# Power.net
KiCad netlist of a schematic drawn in Altium Designer
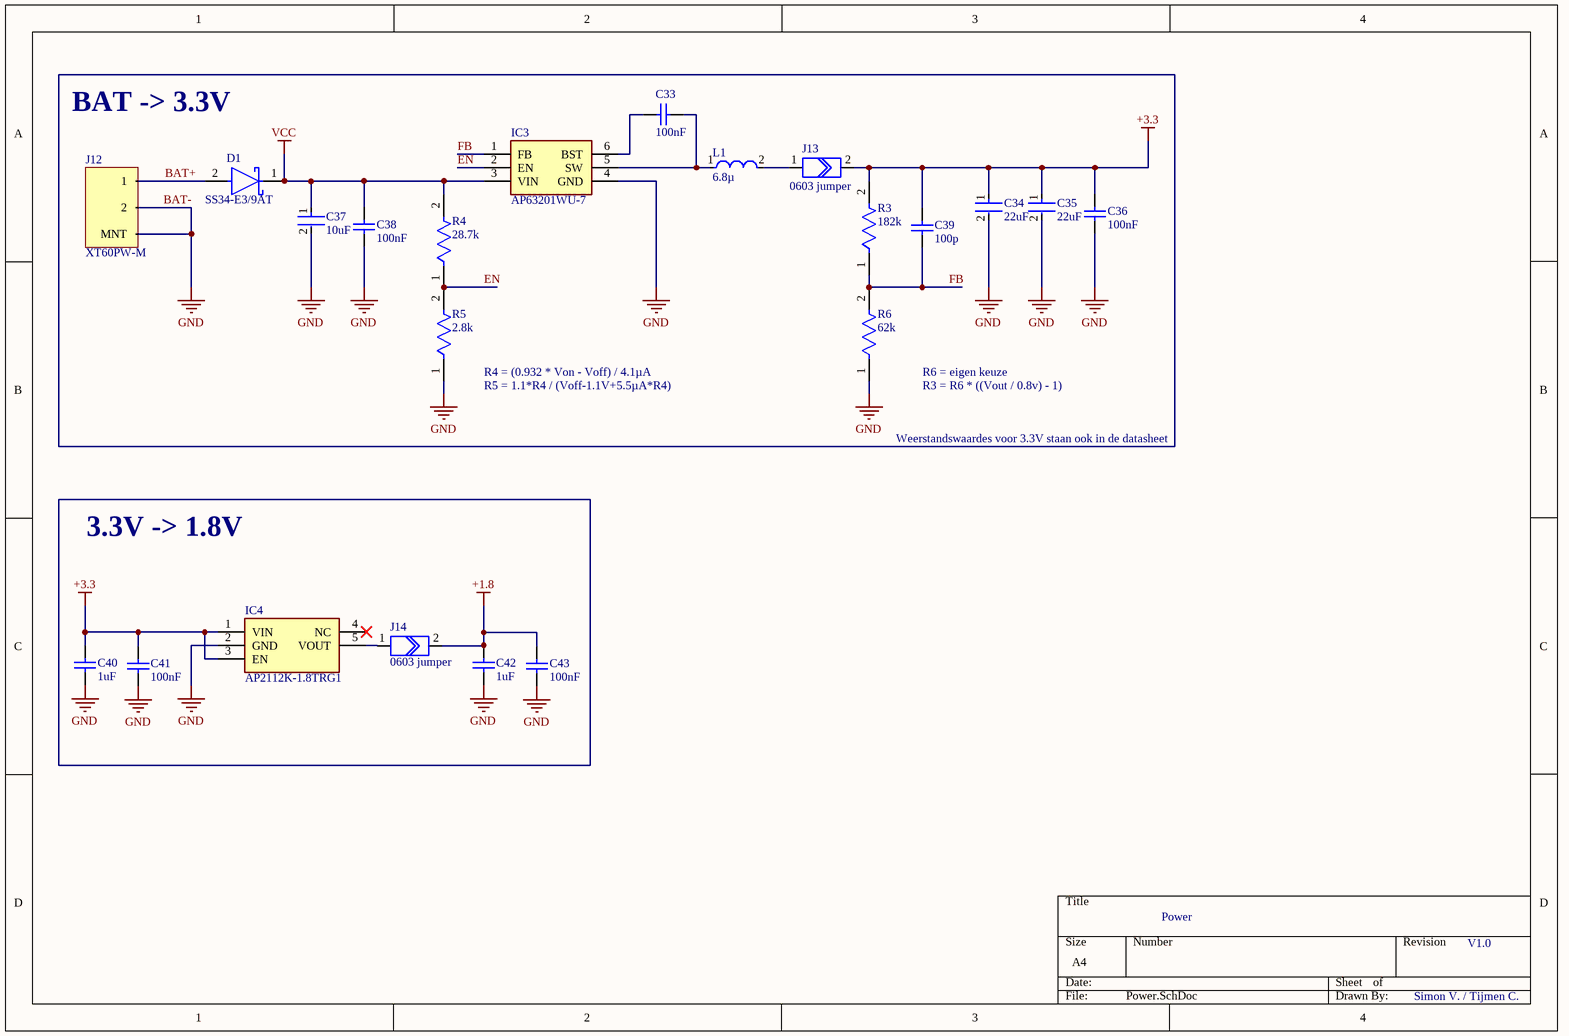
[diagram p0: Power.SchDoc]

(export (version "E")
  (design (tool "Eeschema 10.0.6"))
  (components
    (comp (ref "C33")
      (value "100nF")
      (footprint "CAPC1608X92X38ML15T08")
      (fields (field (name "PART NUMBER") "VJ0603Y104MXXAC") (field (name "MANUFACTURER") "Vitramon"))
      (libsource (lib "Altium Content Vault") (part "CAP"))
    )
    (comp (ref "C34")
      (value "22uF")
      (footprint "FP-GRM188-0_2-IPC_A")
      (description "Multilayer Ceramic Capacitor 22uF 20% 16V X5R 0603 Paper T/R")
      (libsource (lib "Altium Content Vault") (part "02cd4be3c70576c341d710602a673aa"))
    )
    (comp (ref "C35")
      (value "22uF")
      (footprint "FP-GRM188-0_2-IPC_A")
      (description "Multilayer Ceramic Capacitor 22uF 20% 16V X5R 0603 Paper T/R")
      (libsource (lib "Altium Content Vault") (part "02cd4be3c70576c341d710602a673aa"))
    )
    (comp (ref "C36")
      (value "100nF")
      (footprint "CAPC1608X92X38ML15T08")
      (fields (field (name "PART NUMBER") "VJ0603Y104MXXAC") (field (name "MANUFACTURER") "Vitramon"))
      (libsource (lib "Altium Content Vault") (part "CAP"))
    )
    (comp (ref "C37")
      (value "10uF")
      (footprint "FP-ZRB18AR61E106ME01L-MFG")
      (description "CAP CER 10UF 25V X5R 0603")
      (fields (field (name "VOLTAGE") "25V") (field (name "TOLERANCE") "20%"))
      (libsource (lib "Altium Content Vault") (part "b4654b650e69147ec39a6b967a45e02"))
    )
    (comp (ref "C38")
      (value "100nF")
      (footprint "CAPC1608X92X38ML15T08")
      (fields (field (name "PART NUMBER") "VJ0603Y104MXXAC") (field (name "MANUFACTURER") "Vitramon"))
      (libsource (lib "Altium Content Vault") (part "CAP"))
    )
    (comp (ref "C39")
      (value "100p")
      (footprint "CAPC1608X92X38LL15T08")
      (fields (field (name "MANUFACTURER") "Vitramon") (field (name "PART NUMBER") "VJ0603A101FXAAC"))
      (libsource (lib "Altium Content Vault") (part "CAP"))
    )
    (comp (ref "C40")
      (value "1uF")
      (footprint "CAPC1608X90X35NL15T15")
      (fields
        (field (name "PART NUMBER") "0603YD105MAT2A")
        (field (name "MANUFACTURER") "AVX Interconnect / Elco")
      )
      (libsource (lib "Altium Content Vault") (part "CAP"))
    )
    (comp (ref "C41")
      (value "100nF")
      (footprint "CAPC1608X92X38ML15T08")
      (fields (field (name "PART NUMBER") "VJ0603Y104MXXAC") (field (name "MANUFACTURER") "Vitramon"))
      (libsource (lib "Altium Content Vault") (part "CAP"))
    )
    (comp (ref "C42")
      (value "1uF")
      (footprint "CAPC1608X90X35NL15T15")
      (fields
        (field (name "PART NUMBER") "0603YD105MAT2A")
        (field (name "MANUFACTURER") "AVX Interconnect / Elco")
      )
      (libsource (lib "Altium Content Vault") (part "CAP"))
    )
    (comp (ref "C43")
      (value "100nF")
      (footprint "CAPC1608X92X38ML15T08")
      (fields (field (name "PART NUMBER") "VJ0603Y104MXXAC") (field (name "MANUFACTURER") "Vitramon"))
      (libsource (lib "Altium Content Vault") (part "CAP"))
    )
    (comp (ref "D1")
      (value "SS34-E3/9AT")
      (footprint "FP-SMC-MFG")
      (description "DIODE SCHOTTKY 40V 3A DO214AB")
      (libsource (lib "Altium Content Vault") (part "c1678fac7984e62e0809fbf79c06691"))
    )
    (comp (ref "IC3")
      (value "AP63201WU-7")
      (footprint "SamacSys:SOT95P280X100-6N")
      (description "Integrated Circuit")
      (fields (field (name "MOUSER PART NUMBER") "621-AP63201WU-7"))
      (libsource (lib "*") (part "AP63201WU-7"))
    )
    (comp (ref "IC4")
      (value "AP2112K-1.8TRG1")
      (footprint "SamacSys:SOT95P285X140-5N")
      (description "Integrated Circuit")
      (fields (field (name "MOUSER PART NUMBER") "621-AP2112K-1.8TRG1"))
      (libsource (lib "*") (part "AP2112K-1.8TRG1"))
    )
    (comp (ref "J12")
      (value "XT60PW-M")
      (footprint "XT60 juist")
      (libsource (lib "XT60PW-M") (part "XT60PW-M"))
    )
    (comp (ref "J13")
      (value "0603 jumper")
      (footprint "0603 jumper")
      (libsource (lib "Eigen_schemas") (part "0603 jumper"))
    )
    (comp (ref "J14")
      (value "0603 jumper")
      (footprint "0603 jumper")
      (libsource (lib "Eigen_schemas") (part "0603 jumper"))
    )
    (comp (ref "L1")
      (value "6.8µ")
      (footprint "FP-MLZ1608-IPC_B")
      (description "Shielded Multilayer Inductor 6.8uH ±20% 300mA 962mΩ SMD 0603")
      (libsource (lib "Altium Content Vault") (part "725321dda6339637d4d059423bc1c3c"))
    )
    (comp (ref "R3")
      (value "182k")
      (footprint "FP-AC0603-IPC_B")
      (description "RES 182KΩ 1.00% 0.1W 0603")
      (fields (field (name "TOLERANCE") "1%"))
      (libsource (lib "Altium Content Vault") (part "1029c3af85768c4190bb7ad29bc67b5"))
    )
    (comp (ref "R4")
      (value "28.7k")
      (footprint "FP-TFCR0603-MFG")
      (description "RES Thin Film,  28.7kΩ, 0.1%, 0.1W, 25ppm/°C, 0603")
      (libsource (lib "Altium Content Vault") (part "1029c3af85768c4190bb7ad29bc67b5"))
    )
    (comp (ref "R5")
      (value "2.8k")
      (footprint "FP-CRCW0603-HPe3-IPC_B")
      (description "RES Thick Film, 2.8kΩ, 1%, 0.33W, 100ppm/°C, 0603")
      (fields (field (name "TOLERANCE") "1%"))
      (libsource (lib "Altium Content Vault") (part "1029c3af85768c4190bb7ad29bc67b5"))
    )
    (comp (ref "R6")
      (value "62k")
      (footprint "FP-RMCF0603-IPC_B")
      (description "62kΩ ±5% 0.1W 0603 Thick Film Chip Resistor AEC-Q200 compliant")
      (fields (field (name "TOLERANCE") "5%"))
      (libsource (lib "Altium Content Vault") (part "1029c3af85768c4190bb7ad29bc67b5"))
    )
  )
  (nets
    (net (code "1") (name "+1.8") (class "Default")
      (node (ref "C42") (pin "2") (pinfunction "2_2") (pintype "passive"))
      (node (ref "C43") (pin "1") (pinfunction "1_1") (pintype "passive"))
      (node (ref "J14") (pin "2") (pinfunction "2_2") (pintype "passive"))
    )
    (net (code "2") (name "+3.3") (class "Default")
      (node (ref "C34") (pin "1") (pinfunction "1_1") (pintype "passive"))
      (node (ref "C35") (pin "1") (pinfunction "1_1") (pintype "passive"))
      (node (ref "C36") (pin "2") (pinfunction "2_2") (pintype "passive"))
      (node (ref "C39") (pin "2") (pinfunction "2_2") (pintype "passive"))
      (node (ref "C40") (pin "2") (pinfunction "2_2") (pintype "passive"))
      (node (ref "C41") (pin "1") (pinfunction "1_1") (pintype "passive"))
      (node (ref "IC4") (pin "1") (pinfunction "VIN_1") (pintype "passive"))
      (node (ref "IC4") (pin "3") (pinfunction "EN_3") (pintype "passive"))
      (node (ref "J13") (pin "2") (pinfunction "2_2") (pintype "passive"))
      (node (ref "R3") (pin "2") (pinfunction "2_2") (pintype "passive"))
    )
    (net (code "3") (name "/BAT+") (class "Default")
      (node (ref "D1") (pin "2") (pinfunction "A_2") (pintype "passive"))
      (node (ref "J12") (pin "1") (pinfunction "1_1") (pintype "passive"))
    )
    (net (code "4") (name "/EN") (class "Default")
      (node (ref "IC3") (pin "2") (pinfunction "EN_2") (pintype "passive"))
      (node (ref "R4") (pin "1") (pinfunction "1_1") (pintype "passive"))
      (node (ref "R5") (pin "2") (pinfunction "2_2") (pintype "passive"))
    )
    (net (code "5") (name "/FB") (class "Default")
      (node (ref "C39") (pin "1") (pinfunction "1_1") (pintype "passive"))
      (node (ref "IC3") (pin "1") (pinfunction "FB_1") (pintype "passive"))
      (node (ref "R3") (pin "1") (pinfunction "1_1") (pintype "passive"))
      (node (ref "R6") (pin "2") (pinfunction "2_2") (pintype "passive"))
    )
    (net (code "6") (name "GND") (class "Default")
      (node (ref "C34") (pin "2") (pinfunction "2_2") (pintype "passive"))
      (node (ref "C35") (pin "2") (pinfunction "2_2") (pintype "passive"))
      (node (ref "C36") (pin "1") (pinfunction "1_1") (pintype "passive"))
      (node (ref "C37") (pin "2") (pinfunction "2_2") (pintype "passive"))
      (node (ref "C38") (pin "1") (pinfunction "1_1") (pintype "passive"))
      (node (ref "C40") (pin "1") (pinfunction "1_1") (pintype "passive"))
      (node (ref "C41") (pin "2") (pinfunction "2_2") (pintype "passive"))
      (node (ref "C42") (pin "1") (pinfunction "1_1") (pintype "passive"))
      (node (ref "C43") (pin "2") (pinfunction "2_2") (pintype "passive"))
      (node (ref "IC3") (pin "4") (pinfunction "GND_4") (pintype "passive"))
      (node (ref "IC4") (pin "2") (pinfunction "GND_2") (pintype "passive"))
      (node (ref "J12") (pin "2") (pinfunction "2_2") (pintype "passive"))
      (node (ref "J12") (pin "MNT") (pinfunction "MNT_MNT") (pintype "passive"))
      (node (ref "R5") (pin "1") (pinfunction "1_1") (pintype "passive"))
      (node (ref "R6") (pin "1") (pinfunction "1_1") (pintype "passive"))
    )
    (net (code "7") (name "Net-(IC3-BST)") (class "Default")
      (node (ref "C33") (pin "2") (pinfunction "2_2") (pintype "passive"))
      (node (ref "IC3") (pin "6") (pinfunction "BST_6") (pintype "passive"))
    )
    (net (code "8") (name "Net-(IC3-SW)") (class "Default")
      (node (ref "C33") (pin "1") (pinfunction "1_1") (pintype "passive"))
      (node (ref "IC3") (pin "5") (pinfunction "SW_5") (pintype "passive"))
      (node (ref "L1") (pin "1") (pinfunction "1_1") (pintype "passive"))
    )
    (net (code "9") (name "Net-(IC4-VOUT)") (class "Default")
      (node (ref "IC4") (pin "5") (pinfunction "VOUT_5") (pintype "passive"))
      (node (ref "J14") (pin "1") (pinfunction "1_1") (pintype "passive"))
    )
    (net (code "10") (name "Net-(J13-Pad1)") (class "Default")
      (node (ref "J13") (pin "1") (pinfunction "1_1") (pintype "passive"))
      (node (ref "L1") (pin "2") (pinfunction "2_2") (pintype "passive"))
    )
    (net (code "11") (name "VCC") (class "Default")
      (node (ref "C37") (pin "1") (pinfunction "1_1") (pintype "passive"))
      (node (ref "C38") (pin "2") (pinfunction "2_2") (pintype "passive"))
      (node (ref "D1") (pin "1") (pinfunction "C_1") (pintype "passive"))
      (node (ref "IC3") (pin "3") (pinfunction "VIN_3") (pintype "passive"))
      (node (ref "R4") (pin "2") (pinfunction "2_2") (pintype "passive"))
    )
    (net (code "12") (name "unconnected-(IC4-NC-Pad4)") (class "Default")
      (node (ref "IC4") (pin "4") (pinfunction "NC_4") (pintype "passive+no_connect"))
    )
  )
)
